# Ripple_PMS.net
KiCad netlist of a schematic drawn in Altium Designer
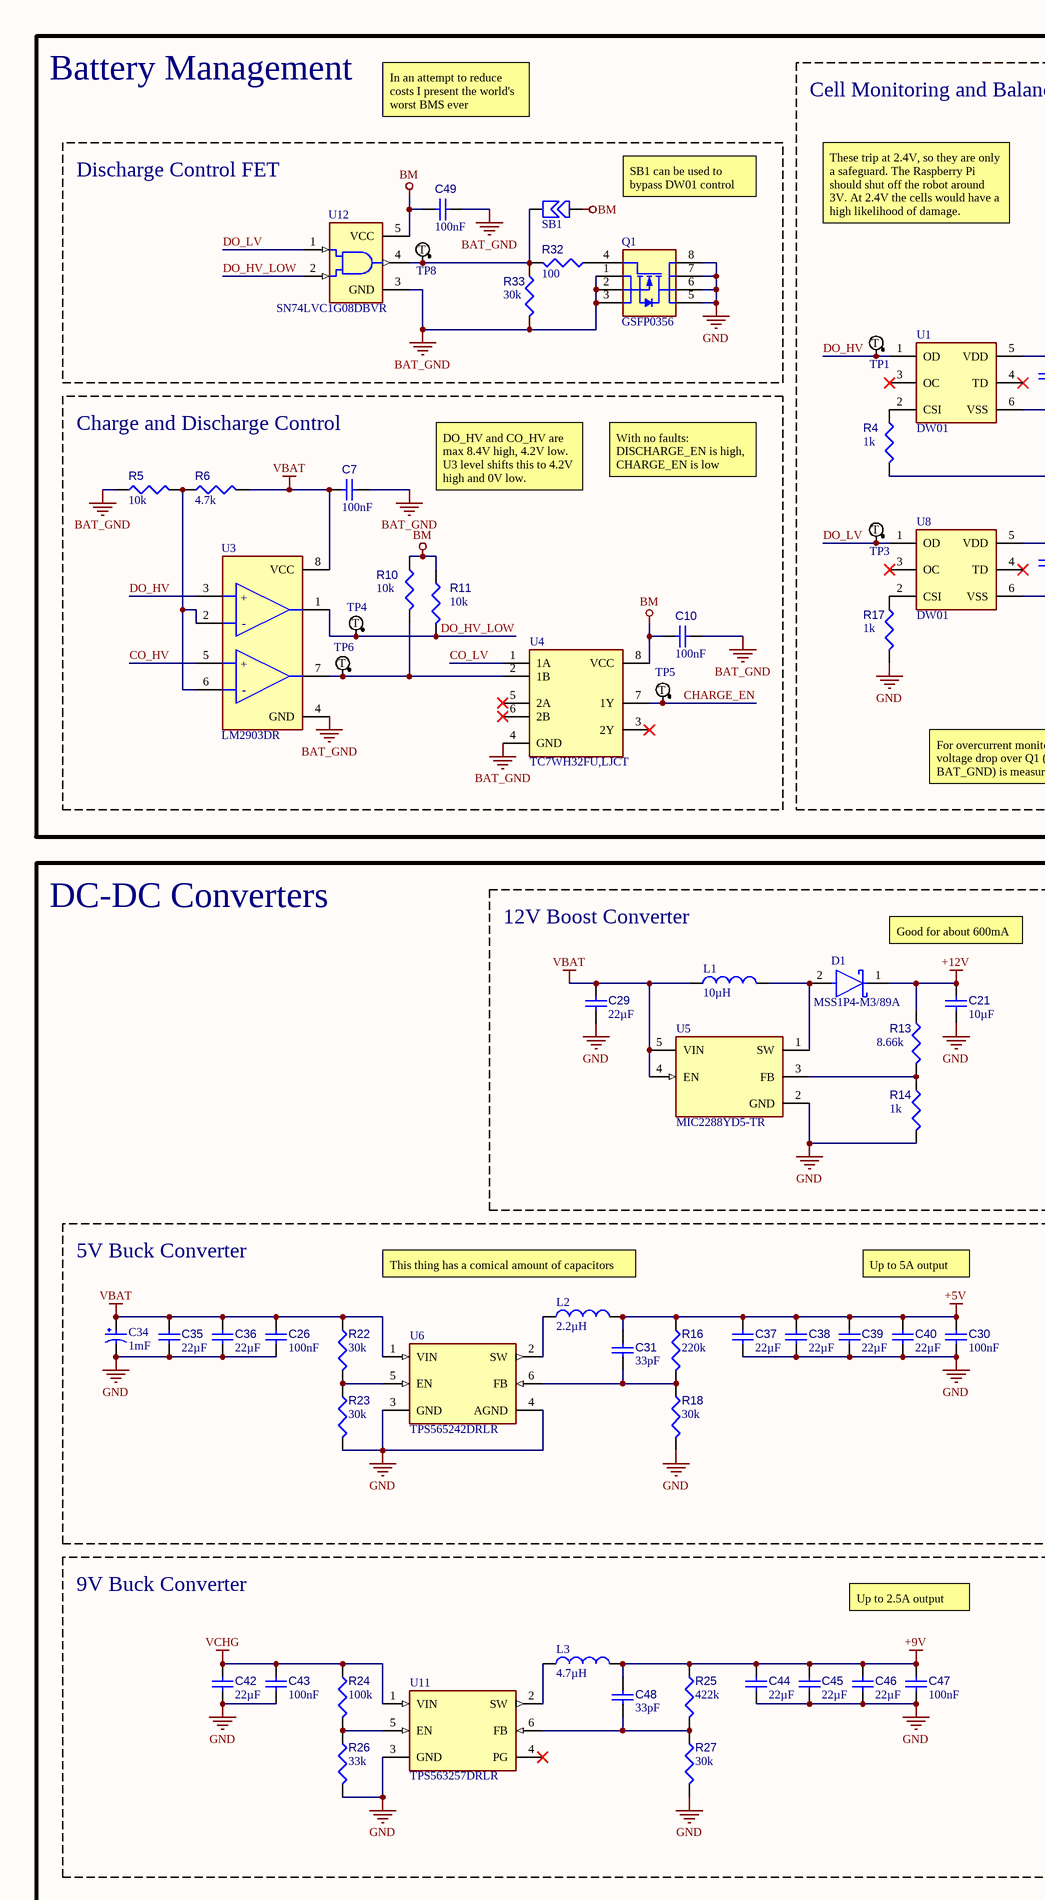
[diagram p0: Ripple_PMS.SchDoc, left]
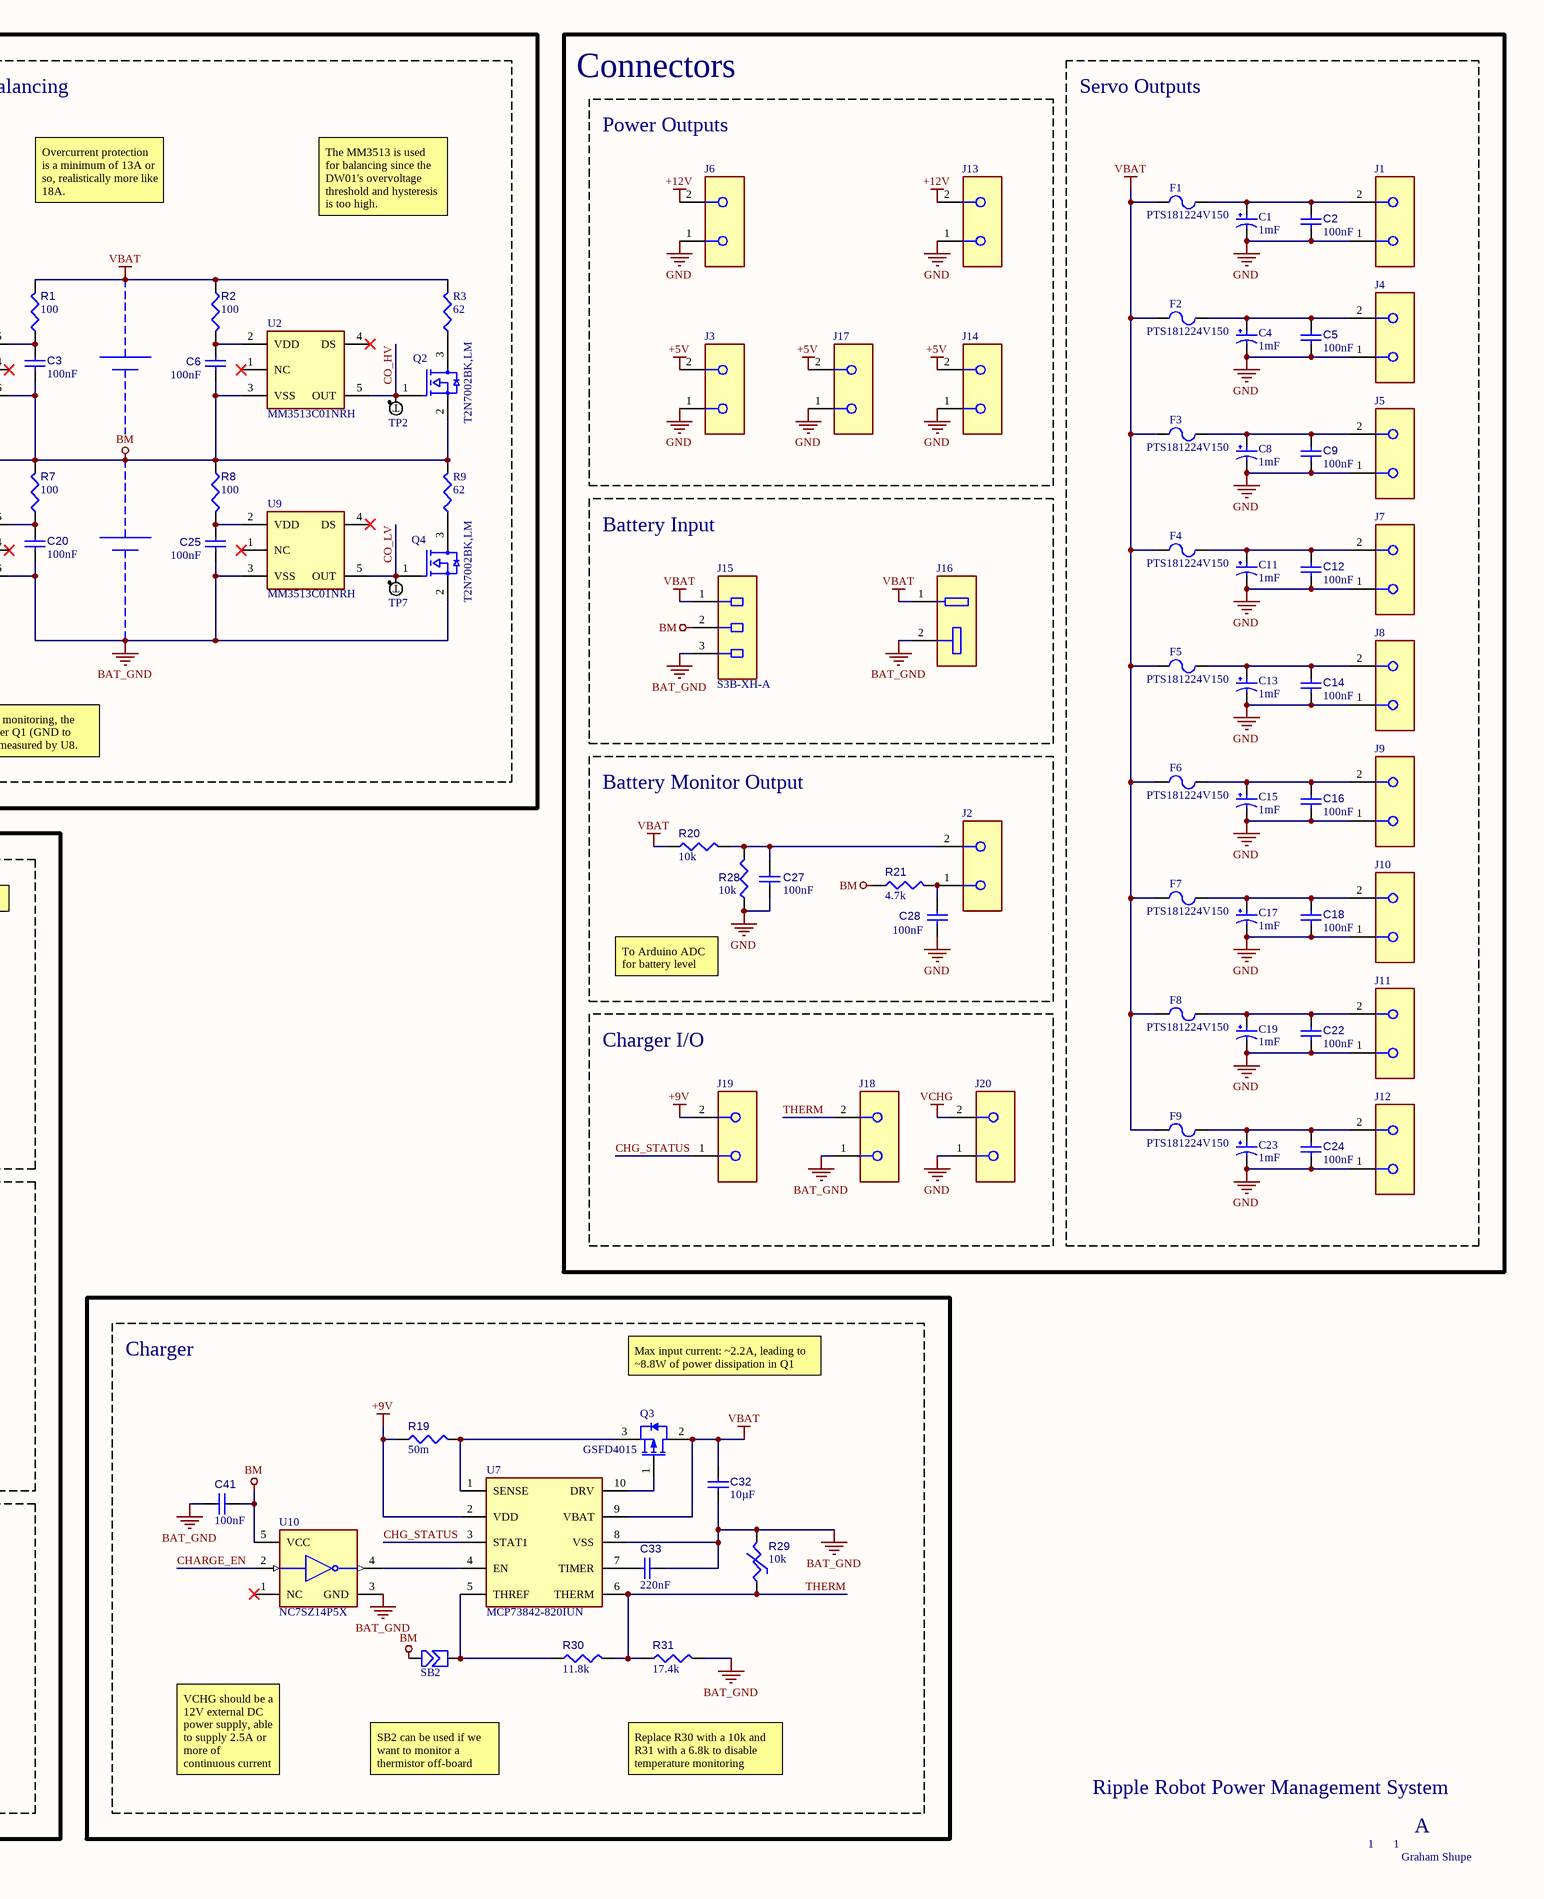
[diagram p1: Ripple_PMS.SchDoc, right]

(export (version "E")
  (design (tool "Eeschema 10.0.6"))
  (components
    (comp (ref "C1")
      (value "1mF")
      (footprint "CAP_YX_10X16_RUB")
      (description "Description")
      (fields
        (field (name "MANUFACTURER_PART_NUMBER") "16ZLH1000MEFC10X16")
        (field (name "COPYRIGHT") "Copyright (C) 2025 Ultra Librarian. All rights reserved.")
      )
      (libsource (lib "Graham Shupe") (part "16ZLH1000MEFC10X16"))
    )
    (comp (ref "C2")
      (value "100nF")
      (footprint "CAPC2013X95X50LL10T25")
      (description "Chip Capacitor, 100 nF, +/- 10%, 50 V, 0805 (2012 Metric)")
      (fields (field (name "TOLERANCE") "10%") (field (name "Comment") "Capacitor 100 nF +/-10% 50 V 0805"))
      (libsource (lib "Graham Shupe") (part "CAP-NP-2"))
    )
    (comp (ref "C3")
      (value "100nF")
      (footprint "CAPC2013X95X50LL10T25")
      (description "Chip Capacitor, 100 nF, +/- 10%, 50 V, 0805 (2012 Metric)")
      (fields (field (name "TOLERANCE") "10%") (field (name "Comment") "Capacitor 100 nF +/-10% 50 V 0805"))
      (libsource (lib "Graham Shupe") (part "CAP-NP-2"))
    )
    (comp (ref "C4")
      (value "1mF")
      (footprint "CAP_YX_10X16_RUB")
      (description "Description")
      (fields
        (field (name "MANUFACTURER_PART_NUMBER") "16ZLH1000MEFC10X16")
        (field (name "COPYRIGHT") "Copyright (C) 2025 Ultra Librarian. All rights reserved.")
      )
      (libsource (lib "Graham Shupe") (part "16ZLH1000MEFC10X16"))
    )
    (comp (ref "C5")
      (value "100nF")
      (footprint "CAPC2013X95X50LL10T25")
      (description "Chip Capacitor, 100 nF, +/- 10%, 50 V, 0805 (2012 Metric)")
      (fields (field (name "TOLERANCE") "10%") (field (name "Comment") "Capacitor 100 nF +/-10% 50 V 0805"))
      (libsource (lib "Graham Shupe") (part "CAP-NP-2"))
    )
    (comp (ref "C6")
      (value "100nF")
      (footprint "CAPC2013X95X50LL10T25")
      (description "Chip Capacitor, 100 nF, +/- 10%, 50 V, 0805 (2012 Metric)")
      (fields (field (name "TOLERANCE") "10%") (field (name "Comment") "Capacitor 100 nF +/-10% 50 V 0805"))
      (libsource (lib "Graham Shupe") (part "CAP-NP-2"))
    )
    (comp (ref "C7")
      (value "100nF")
      (footprint "CAPC2013X95X50LL10T25")
      (description "Chip Capacitor, 100 nF, +/- 10%, 50 V, 0805 (2012 Metric)")
      (fields (field (name "TOLERANCE") "10%") (field (name "Comment") "Capacitor 100 nF +/-10% 50 V 0805"))
      (libsource (lib "Graham Shupe") (part "CAP-NP-2"))
    )
    (comp (ref "C8")
      (value "1mF")
      (footprint "CAP_YX_10X16_RUB")
      (description "Description")
      (fields
        (field (name "MANUFACTURER_PART_NUMBER") "16ZLH1000MEFC10X16")
        (field (name "COPYRIGHT") "Copyright (C) 2025 Ultra Librarian. All rights reserved.")
      )
      (libsource (lib "Graham Shupe") (part "16ZLH1000MEFC10X16"))
    )
    (comp (ref "C9")
      (value "100nF")
      (footprint "CAPC2013X95X50LL10T25")
      (description "Chip Capacitor, 100 nF, +/- 10%, 50 V, 0805 (2012 Metric)")
      (fields (field (name "TOLERANCE") "10%") (field (name "Comment") "Capacitor 100 nF +/-10% 50 V 0805"))
      (libsource (lib "Graham Shupe") (part "CAP-NP-2"))
    )
    (comp (ref "C10")
      (value "100nF")
      (footprint "CAPC2013X95X50LL10T25")
      (description "Chip Capacitor, 100 nF, +/- 10%, 50 V, 0805 (2012 Metric)")
      (fields (field (name "TOLERANCE") "10%") (field (name "Comment") "Capacitor 100 nF +/-10% 50 V 0805"))
      (libsource (lib "Graham Shupe") (part "CAP-NP-2"))
    )
    (comp (ref "C11")
      (value "1mF")
      (footprint "CAP_YX_10X16_RUB")
      (description "Description")
      (fields
        (field (name "MANUFACTURER_PART_NUMBER") "16ZLH1000MEFC10X16")
        (field (name "COPYRIGHT") "Copyright (C) 2025 Ultra Librarian. All rights reserved.")
      )
      (libsource (lib "Graham Shupe") (part "16ZLH1000MEFC10X16"))
    )
    (comp (ref "C12")
      (value "100nF")
      (footprint "CAPC2013X95X50LL10T25")
      (description "Chip Capacitor, 100 nF, +/- 10%, 50 V, 0805 (2012 Metric)")
      (fields (field (name "TOLERANCE") "10%") (field (name "Comment") "Capacitor 100 nF +/-10% 50 V 0805"))
      (libsource (lib "Graham Shupe") (part "CAP-NP-2"))
    )
    (comp (ref "C13")
      (value "1mF")
      (footprint "CAP_YX_10X16_RUB")
      (description "Description")
      (fields
        (field (name "MANUFACTURER_PART_NUMBER") "16ZLH1000MEFC10X16")
        (field (name "COPYRIGHT") "Copyright (C) 2025 Ultra Librarian. All rights reserved.")
      )
      (libsource (lib "Graham Shupe") (part "16ZLH1000MEFC10X16"))
    )
    (comp (ref "C14")
      (value "100nF")
      (footprint "CAPC2013X95X50LL10T25")
      (description "Chip Capacitor, 100 nF, +/- 10%, 50 V, 0805 (2012 Metric)")
      (fields (field (name "TOLERANCE") "10%") (field (name "Comment") "Capacitor 100 nF +/-10% 50 V 0805"))
      (libsource (lib "Graham Shupe") (part "CAP-NP-2"))
    )
    (comp (ref "C15")
      (value "1mF")
      (footprint "CAP_YX_10X16_RUB")
      (description "Description")
      (fields
        (field (name "MANUFACTURER_PART_NUMBER") "16ZLH1000MEFC10X16")
        (field (name "COPYRIGHT") "Copyright (C) 2025 Ultra Librarian. All rights reserved.")
      )
      (libsource (lib "Graham Shupe") (part "16ZLH1000MEFC10X16"))
    )
    (comp (ref "C16")
      (value "100nF")
      (footprint "CAPC2013X95X50LL10T25")
      (description "Chip Capacitor, 100 nF, +/- 10%, 50 V, 0805 (2012 Metric)")
      (fields (field (name "TOLERANCE") "10%") (field (name "Comment") "Capacitor 100 nF +/-10% 50 V 0805"))
      (libsource (lib "Graham Shupe") (part "CAP-NP-2"))
    )
    (comp (ref "C17")
      (value "1mF")
      (footprint "CAP_YX_10X16_RUB")
      (description "Description")
      (fields
        (field (name "MANUFACTURER_PART_NUMBER") "16ZLH1000MEFC10X16")
        (field (name "COPYRIGHT") "Copyright (C) 2025 Ultra Librarian. All rights reserved.")
      )
      (libsource (lib "Graham Shupe") (part "16ZLH1000MEFC10X16"))
    )
    (comp (ref "C18")
      (value "100nF")
      (footprint "CAPC2013X95X50LL10T25")
      (description "Chip Capacitor, 100 nF, +/- 10%, 50 V, 0805 (2012 Metric)")
      (fields (field (name "TOLERANCE") "10%") (field (name "Comment") "Capacitor 100 nF +/-10% 50 V 0805"))
      (libsource (lib "Graham Shupe") (part "CAP-NP-2"))
    )
    (comp (ref "C19")
      (value "1mF")
      (footprint "CAP_YX_10X16_RUB")
      (description "Description")
      (fields
        (field (name "MANUFACTURER_PART_NUMBER") "16ZLH1000MEFC10X16")
        (field (name "COPYRIGHT") "Copyright (C) 2025 Ultra Librarian. All rights reserved.")
      )
      (libsource (lib "Graham Shupe") (part "16ZLH1000MEFC10X16"))
    )
    (comp (ref "C20")
      (value "100nF")
      (footprint "CAPC2013X95X50LL10T25")
      (description "Chip Capacitor, 100 nF, +/- 10%, 50 V, 0805 (2012 Metric)")
      (fields (field (name "TOLERANCE") "10%") (field (name "Comment") "Capacitor 100 nF +/-10% 50 V 0805"))
      (libsource (lib "Graham Shupe") (part "CAP-NP-2"))
    )
    (comp (ref "C21")
      (value "10µF")
      (footprint "CAPC0805(2012)145_L")
      (description "Chip Capacitor, 10µF +/-20%, 25V, 0805, Thickness 1.45 mm")
      (fields (field (name "TOLERANCE") "10%") (field (name "Comment") "Capacitor 10µF +/-20% 25V 0805"))
      (libsource (lib "Graham Shupe") (part "CAP-NP-2"))
    )
    (comp (ref "C22")
      (value "100nF")
      (footprint "CAPC2013X95X50LL10T25")
      (description "Chip Capacitor, 100 nF, +/- 10%, 50 V, 0805 (2012 Metric)")
      (fields (field (name "TOLERANCE") "10%") (field (name "Comment") "Capacitor 100 nF +/-10% 50 V 0805"))
      (libsource (lib "Graham Shupe") (part "CAP-NP-2"))
    )
    (comp (ref "C23")
      (value "1mF")
      (footprint "CAP_YX_10X16_RUB")
      (description "Description")
      (fields
        (field (name "MANUFACTURER_PART_NUMBER") "16ZLH1000MEFC10X16")
        (field (name "COPYRIGHT") "Copyright (C) 2025 Ultra Librarian. All rights reserved.")
      )
      (libsource (lib "Graham Shupe") (part "16ZLH1000MEFC10X16"))
    )
    (comp (ref "C24")
      (value "100nF")
      (footprint "CAPC2013X95X50LL10T25")
      (description "Chip Capacitor, 100 nF, +/- 10%, 50 V, 0805 (2012 Metric)")
      (fields (field (name "TOLERANCE") "10%") (field (name "Comment") "Capacitor 100 nF +/-10% 50 V 0805"))
      (libsource (lib "Graham Shupe") (part "CAP-NP-2"))
    )
    (comp (ref "C25")
      (value "100nF")
      (footprint "CAPC2013X95X50LL10T25")
      (description "Chip Capacitor, 100 nF, +/- 10%, 50 V, 0805 (2012 Metric)")
      (fields (field (name "TOLERANCE") "10%") (field (name "Comment") "Capacitor 100 nF +/-10% 50 V 0805"))
      (libsource (lib "Graham Shupe") (part "CAP-NP-2"))
    )
    (comp (ref "C26")
      (value "100nF")
      (footprint "CAPC2013X95X50LL10T25")
      (description "Chip Capacitor, 100 nF, +/- 10%, 50 V, 0805 (2012 Metric)")
      (fields (field (name "TOLERANCE") "10%") (field (name "Comment") "Capacitor 100 nF +/-10% 50 V 0805"))
      (libsource (lib "Graham Shupe") (part "CAP-NP-2"))
    )
    (comp (ref "C27")
      (value "100nF")
      (footprint "CAPC2013X95X50LL10T25")
      (description "Chip Capacitor, 100 nF, +/- 10%, 50 V, 0805 (2012 Metric)")
      (fields (field (name "TOLERANCE") "10%") (field (name "Comment") "Capacitor 100 nF +/-10% 50 V 0805"))
      (libsource (lib "Graham Shupe") (part "CAP-NP-2"))
    )
    (comp (ref "C28")
      (value "100nF")
      (footprint "CAPC2013X95X50LL10T25")
      (description "Chip Capacitor, 100 nF, +/- 10%, 50 V, 0805 (2012 Metric)")
      (fields (field (name "TOLERANCE") "10%") (field (name "Comment") "Capacitor 100 nF +/-10% 50 V 0805"))
      (libsource (lib "Graham Shupe") (part "CAP-NP-2"))
    )
    (comp (ref "C29")
      (value "22µF")
      (footprint "CAPC0805(2012)145_L")
      (description "Chip Capacitor, 22µF +/-40%, 16V, 0805, Thickness 1.45 mm")
      (fields (field (name "TOLERANCE") "5%") (field (name "Comment") "Capacitor 22µF +/-40% 16V 0805"))
      (libsource (lib "Graham Shupe") (part "CAP-NP-2"))
    )
    (comp (ref "C30")
      (value "100nF")
      (footprint "CAPC2013X95X50LL10T25")
      (description "Chip Capacitor, 100 nF, +/- 10%, 50 V, 0805 (2012 Metric)")
      (fields (field (name "TOLERANCE") "10%") (field (name "Comment") "Capacitor 100 nF +/-10% 50 V 0805"))
      (libsource (lib "Graham Shupe") (part "CAP-NP-2"))
    )
    (comp (ref "C31")
      (value "33pF")
      (footprint "RESC2012X06N")
      (description "0805 33pF")
      (fields (field (name "Comment") "33 pF Capacitor"))
      (libsource (lib "Graham Shupe") (part "CAP-NP-2"))
    )
    (comp (ref "C32")
      (value "10µF")
      (footprint "CAPC0805(2012)145_L")
      (description "Chip Capacitor, 10µF +/-20%, 25V, 0805, Thickness 1.45 mm")
      (fields (field (name "TOLERANCE") "10%") (field (name "Comment") "Capacitor 10µF +/-20% 25V 0805"))
      (libsource (lib "Graham Shupe") (part "CAP-NP-2"))
    )
    (comp (ref "C33")
      (value "220nF")
      (footprint "RESC2012X06N")
      (description "0.22 uF")
      (fields (field (name "Comment") "220 nF Capacitor"))
      (libsource (lib "Graham Shupe") (part "CAP-NP-2"))
    )
    (comp (ref "C34")
      (value "1mF")
      (footprint "CAP_YX_10X16_RUB")
      (description "Description")
      (fields
        (field (name "MANUFACTURER_PART_NUMBER") "16ZLH1000MEFC10X16")
        (field (name "COPYRIGHT") "Copyright (C) 2025 Ultra Librarian. All rights reserved.")
      )
      (libsource (lib "Graham Shupe") (part "16ZLH1000MEFC10X16"))
    )
    (comp (ref "C35")
      (value "22µF")
      (footprint "CAPC0805(2012)145_L")
      (description "Chip Capacitor, 22µF +/-40%, 16V, 0805, Thickness 1.45 mm")
      (fields (field (name "TOLERANCE") "5%") (field (name "Comment") "Capacitor 22µF +/-40% 16V 0805"))
      (libsource (lib "Graham Shupe") (part "CAP-NP-2"))
    )
    (comp (ref "C36")
      (value "22µF")
      (footprint "CAPC0805(2012)145_L")
      (description "Chip Capacitor, 22µF +/-40%, 16V, 0805, Thickness 1.45 mm")
      (fields (field (name "TOLERANCE") "5%") (field (name "Comment") "Capacitor 22µF +/-40% 16V 0805"))
      (libsource (lib "Graham Shupe") (part "CAP-NP-2"))
    )
    (comp (ref "C37")
      (value "22µF")
      (footprint "CAPC0805(2012)145_L")
      (description "Chip Capacitor, 22µF +/-40%, 16V, 0805, Thickness 1.45 mm")
      (fields (field (name "TOLERANCE") "5%") (field (name "Comment") "Capacitor 22µF +/-40% 16V 0805"))
      (libsource (lib "Graham Shupe") (part "CAP-NP-2"))
    )
    (comp (ref "C38")
      (value "22µF")
      (footprint "CAPC0805(2012)145_L")
      (description "Chip Capacitor, 22µF +/-40%, 16V, 0805, Thickness 1.45 mm")
      (fields (field (name "TOLERANCE") "5%") (field (name "Comment") "Capacitor 22µF +/-40% 16V 0805"))
      (libsource (lib "Graham Shupe") (part "CAP-NP-2"))
    )
    (comp (ref "C39")
      (value "22µF")
      (footprint "CAPC0805(2012)145_L")
      (description "Chip Capacitor, 22µF +/-40%, 16V, 0805, Thickness 1.45 mm")
      (fields (field (name "TOLERANCE") "5%") (field (name "Comment") "Capacitor 22µF +/-40% 16V 0805"))
      (libsource (lib "Graham Shupe") (part "CAP-NP-2"))
    )
    (comp (ref "C40")
      (value "22µF")
      (footprint "CAPC0805(2012)145_L")
      (description "Chip Capacitor, 22µF +/-40%, 16V, 0805, Thickness 1.45 mm")
      (fields (field (name "TOLERANCE") "5%") (field (name "Comment") "Capacitor 22µF +/-40% 16V 0805"))
      (libsource (lib "Graham Shupe") (part "CAP-NP-2"))
    )
    (comp (ref "C41")
      (value "100nF")
      (footprint "CAPC2013X95X50LL10T25")
      (description "Chip Capacitor, 100 nF, +/- 10%, 50 V, 0805 (2012 Metric)")
      (fields (field (name "TOLERANCE") "10%") (field (name "Comment") "Capacitor 100 nF +/-10% 50 V 0805"))
      (libsource (lib "Graham Shupe") (part "CAP-NP-2"))
    )
    (comp (ref "C42")
      (value "22µF")
      (footprint "CAPC0805(2012)145_L")
      (description "Chip Capacitor, 22µF +/-40%, 16V, 0805, Thickness 1.45 mm")
      (fields (field (name "TOLERANCE") "5%") (field (name "Comment") "Capacitor 22µF +/-40% 16V 0805"))
      (libsource (lib "Graham Shupe") (part "CAP-NP-2"))
    )
    (comp (ref "C43")
      (value "100nF")
      (footprint "CAPC2013X95X50LL10T25")
      (description "Chip Capacitor, 100 nF, +/- 10%, 50 V, 0805 (2012 Metric)")
      (fields (field (name "TOLERANCE") "10%") (field (name "Comment") "Capacitor 100 nF +/-10% 50 V 0805"))
      (libsource (lib "Graham Shupe") (part "CAP-NP-2"))
    )
    (comp (ref "C44")
      (value "22µF")
      (footprint "CAPC0805(2012)145_L")
      (description "Chip Capacitor, 22µF +/-40%, 16V, 0805, Thickness 1.45 mm")
      (fields (field (name "TOLERANCE") "5%") (field (name "Comment") "Capacitor 22µF +/-40% 16V 0805"))
      (libsource (lib "Graham Shupe") (part "CAP-NP-2"))
    )
    (comp (ref "C45")
      (value "22µF")
      (footprint "CAPC0805(2012)145_L")
      (description "Chip Capacitor, 22µF +/-40%, 16V, 0805, Thickness 1.45 mm")
      (fields (field (name "TOLERANCE") "5%") (field (name "Comment") "Capacitor 22µF +/-40% 16V 0805"))
      (libsource (lib "Graham Shupe") (part "CAP-NP-2"))
    )
    (comp (ref "C46")
      (value "22µF")
      (footprint "CAPC0805(2012)145_L")
      (description "Chip Capacitor, 22µF +/-40%, 16V, 0805, Thickness 1.45 mm")
      (fields (field (name "TOLERANCE") "5%") (field (name "Comment") "Capacitor 22µF +/-40% 16V 0805"))
      (libsource (lib "Graham Shupe") (part "CAP-NP-2"))
    )
    (comp (ref "C47")
      (value "100nF")
      (footprint "CAPC2013X95X50LL10T25")
      (description "Chip Capacitor, 100 nF, +/- 10%, 50 V, 0805 (2012 Metric)")
      (fields (field (name "TOLERANCE") "10%") (field (name "Comment") "Capacitor 100 nF +/-10% 50 V 0805"))
      (libsource (lib "Graham Shupe") (part "CAP-NP-2"))
    )
    (comp (ref "C48")
      (value "33pF")
      (footprint "RESC2012X06N")
      (description "0805 33pF")
      (fields (field (name "Comment") "33 pF Capacitor"))
      (libsource (lib "Graham Shupe") (part "CAP-NP-2"))
    )
    (comp (ref "C49")
      (value "100nF")
      (footprint "CAPC2013X95X50LL10T25")
      (description "Chip Capacitor, 100 nF, +/- 10%, 50 V, 0805 (2012 Metric)")
      (fields (field (name "TOLERANCE") "10%") (field (name "Comment") "Capacitor 100 nF +/-10% 50 V 0805"))
      (libsource (lib "Graham Shupe") (part "CAP-NP-2"))
    )
    (comp (ref "D1")
      (value "MSS1P4-M3/89A")
      (footprint "FP-96591-MFG")
      (description "DIODE SCHOTTKY 40V 1A MICROSMP")
      (fields
        (field (name "OCTOPART") "https://octopart.com/mss1p4-m3%2F89a-vishay-42505723")
        (field (name "MANUFACTURER") "Vishay")
      )
      (libsource (lib "Altium Content Vault") (part "c1678fac7984e62e0809fbf79c06691"))
    )
    (comp (ref "F1")
      (value "PTS181224V150")
      (footprint "FUSE_PTS18126_COB")
      (description "1.5A hold 3A trip")
      (fields
        (field (name "MANUFACTURER_PART_NUMBER") "PTS18126V300")
        (field (name "COPYRIGHT") "Copyright (C) 2025 Ultra Librarian. All rights reserved.")
      )
      (libsource (lib "Graham Shupe") (part "PTS18126V300"))
    )
    (comp (ref "F2")
      (value "PTS181224V150")
      (footprint "FUSE_PTS18126_COB")
      (description "1.5A hold 3A trip")
      (fields
        (field (name "MANUFACTURER_PART_NUMBER") "PTS18126V300")
        (field (name "COPYRIGHT") "Copyright (C) 2025 Ultra Librarian. All rights reserved.")
      )
      (libsource (lib "Graham Shupe") (part "PTS18126V300"))
    )
    (comp (ref "F3")
      (value "PTS181224V150")
      (footprint "FUSE_PTS18126_COB")
      (description "1.5A hold 3A trip")
      (fields
        (field (name "MANUFACTURER_PART_NUMBER") "PTS18126V300")
        (field (name "COPYRIGHT") "Copyright (C) 2025 Ultra Librarian. All rights reserved.")
      )
      (libsource (lib "Graham Shupe") (part "PTS18126V300"))
    )
    (comp (ref "F4")
      (value "PTS181224V150")
      (footprint "FUSE_PTS18126_COB")
      (description "1.5A hold 3A trip")
      (fields
        (field (name "MANUFACTURER_PART_NUMBER") "PTS18126V300")
        (field (name "COPYRIGHT") "Copyright (C) 2025 Ultra Librarian. All rights reserved.")
      )
      (libsource (lib "Graham Shupe") (part "PTS18126V300"))
    )
    (comp (ref "F5")
      (value "PTS181224V150")
      (footprint "FUSE_PTS18126_COB")
      (description "1.5A hold 3A trip")
      (fields
        (field (name "MANUFACTURER_PART_NUMBER") "PTS18126V300")
        (field (name "COPYRIGHT") "Copyright (C) 2025 Ultra Librarian. All rights reserved.")
      )
      (libsource (lib "Graham Shupe") (part "PTS18126V300"))
    )
    (comp (ref "F6")
      (value "PTS181224V150")
      (footprint "FUSE_PTS18126_COB")
      (description "1.5A hold 3A trip")
      (fields
        (field (name "MANUFACTURER_PART_NUMBER") "PTS18126V300")
        (field (name "COPYRIGHT") "Copyright (C) 2025 Ultra Librarian. All rights reserved.")
      )
      (libsource (lib "Graham Shupe") (part "PTS18126V300"))
    )
    (comp (ref "F7")
      (value "PTS181224V150")
      (footprint "FUSE_PTS18126_COB")
      (description "1.5A hold 3A trip")
      (fields
        (field (name "MANUFACTURER_PART_NUMBER") "PTS18126V300")
        (field (name "COPYRIGHT") "Copyright (C) 2025 Ultra Librarian. All rights reserved.")
      )
      (libsource (lib "Graham Shupe") (part "PTS18126V300"))
    )
    (comp (ref "F8")
      (value "PTS181224V150")
      (footprint "FUSE_PTS18126_COB")
      (description "1.5A hold 3A trip")
      (fields
        (field (name "MANUFACTURER_PART_NUMBER") "PTS18126V300")
        (field (name "COPYRIGHT") "Copyright (C) 2025 Ultra Librarian. All rights reserved.")
      )
      (libsource (lib "Graham Shupe") (part "PTS18126V300"))
    )
    (comp (ref "F9")
      (value "PTS181224V150")
      (footprint "FUSE_PTS18126_COB")
      (description "1.5A hold 3A trip")
      (fields
        (field (name "MANUFACTURER_PART_NUMBER") "PTS18126V300")
        (field (name "COPYRIGHT") "Copyright (C) 2025 Ultra Librarian. All rights reserved.")
      )
      (libsource (lib "Graham Shupe") (part "PTS18126V300"))
    )
    (comp (ref "J1")
      (value "ServoBreakout2Pin")
      (footprint "New footprint 1")
      (description "for ripple bot")
      (libsource (lib "Graham Shupe") (part "New symbol 1"))
    )
    (comp (ref "J2")
      (value "ServoBreakout2Pin")
      (footprint "New footprint 1")
      (description "for ripple bot")
      (libsource (lib "Graham Shupe") (part "New symbol 1"))
    )
    (comp (ref "J3")
      (value "ServoBreakout2Pin")
      (footprint "New footprint 1")
      (description "for ripple bot")
      (libsource (lib "Graham Shupe") (part "New symbol 1"))
    )
    (comp (ref "J4")
      (value "ServoBreakout2Pin")
      (footprint "New footprint 1")
      (description "for ripple bot")
      (libsource (lib "Graham Shupe") (part "New symbol 1"))
    )
    (comp (ref "J5")
      (value "ServoBreakout2Pin")
      (footprint "New footprint 1")
      (description "for ripple bot")
      (libsource (lib "Graham Shupe") (part "New symbol 1"))
    )
    (comp (ref "J6")
      (value "ServoBreakout2Pin")
      (footprint "New footprint 1")
      (description "for ripple bot")
      (libsource (lib "Graham Shupe") (part "New symbol 1"))
    )
    (comp (ref "J7")
      (value "ServoBreakout2Pin")
      (footprint "New footprint 1")
      (description "for ripple bot")
      (libsource (lib "Graham Shupe") (part "New symbol 1"))
    )
    (comp (ref "J8")
      (value "ServoBreakout2Pin")
      (footprint "New footprint 1")
      (description "for ripple bot")
      (libsource (lib "Graham Shupe") (part "New symbol 1"))
    )
    (comp (ref "J9")
      (value "ServoBreakout2Pin")
      (footprint "New footprint 1")
      (description "for ripple bot")
      (libsource (lib "Graham Shupe") (part "New symbol 1"))
    )
    (comp (ref "J10")
      (value "ServoBreakout2Pin")
      (footprint "New footprint 1")
      (description "for ripple bot")
      (libsource (lib "Graham Shupe") (part "New symbol 1"))
    )
    (comp (ref "J11")
      (value "ServoBreakout2Pin")
      (footprint "New footprint 1")
      (description "for ripple bot")
      (libsource (lib "Graham Shupe") (part "New symbol 1"))
    )
    (comp (ref "J12")
      (value "ServoBreakout2Pin")
      (footprint "New footprint 1")
      (description "for ripple bot")
      (libsource (lib "Graham Shupe") (part "New symbol 1"))
    )
    (comp (ref "J13")
      (value "ServoBreakout2Pin")
      (footprint "New footprint 1")
      (description "for ripple bot")
      (libsource (lib "Graham Shupe") (part "New symbol 1"))
    )
    (comp (ref "J14")
      (value "ServoBreakout2Pin")
      (footprint "New footprint 1")
      (description "for ripple bot")
      (libsource (lib "Graham Shupe") (part "New symbol 1"))
    )
    (comp (ref "J15")
      (value "S3B-XH-A")
      (footprint "FP-S3B-XH-A-1_LF_SN-MFG")
      (description "Header for PCB; pitch 2.50mm; 3-contacts; THT; male; side entry; 250V/3A")
      (libsource (lib "Graham Shupe") (part "0d3f023dd272f625e17a2be33dea85f"))
    )
    (comp (ref "J16")
      (value "Deans Connector")
      (footprint "Deans Connector-Footprint-1")
      (description "T Plug battery connector through-hole")
      (libsource (lib "Graham Shupe") (part "Deans Connector-Symbol-1"))
    )
    (comp (ref "J17")
      (value "ServoBreakout2Pin")
      (footprint "New footprint 1")
      (description "for ripple bot")
      (libsource (lib "Graham Shupe") (part "New symbol 1"))
    )
    (comp (ref "J18")
      (value "ServoBreakout2Pin")
      (footprint "New footprint 1")
      (description "for ripple bot")
      (libsource (lib "Graham Shupe") (part "New symbol 1"))
    )
    (comp (ref "J19")
      (value "ServoBreakout2Pin")
      (footprint "New footprint 1")
      (description "for ripple bot")
      (libsource (lib "Graham Shupe") (part "New symbol 1"))
    )
    (comp (ref "J20")
      (value "ServoBreakout2Pin")
      (footprint "New footprint 1")
      (description "for ripple bot")
      (libsource (lib "Graham Shupe") (part "New symbol 1"))
    )
    (comp (ref "L1")
      (value "10µH")
      (footprint "BOUR-CM322522_V")
      (description "Chip Inductor, 10 uH, +/- 20%, -40 to 125 degC, 1210 (3225 Metric), RoHS, Tape and Reel")
      (fields (field (name "MANUFACTURER") "Bourns") (field (name "Comment") "CBC3225T100MR"))
      (libsource (lib "Graham Shupe") (part "Copy of BOUR-IND-2A"))
    )
    (comp (ref "L2")
      (value "2.2µH")
      (footprint "IND_SDES064T_CYN")
      (description "No Description Available")
      (fields
        (field (name "MANUFACTURER_PART_NUMBER") "SDES064T-2R2MS")
        (field (name "COPYRIGHT") "Copyright (C) 2026 Ultra Librarian. All rights reserved.")
      )
      (libsource (lib "Graham Shupe") (part "SDES064T-2R2MS"))
    )
    (comp (ref "L3")
      (value "4.7µH")
      (footprint "IND_VLS6045EX-4R7M_TDK")
      (description "4.7uH inductor")
      (fields
        (field (name "MANUFACTURER_PART_NUMBER") "VLS6045EX-4R7M")
        (field (name "COPYRIGHT") "Copyright (C) 2025 Ultra Librarian. All rights reserved.")
      )
      (libsource (lib "Graham Shupe") (part "VLS6045EX-4R7M"))
    )
    (comp (ref "Q1")
      (value "GSFP0356")
      (footprint "PPAK5X6-8L_GAS")
      (description "55A N-ch MOSFET, 47W PD@Tc=25")
      (fields
        (field (name "MANUFACTURER_PART_NUMBER") "GSFP1080")
        (field (name "COPYRIGHT") "Copyright (C) 2025 Ultra Librarian. All rights reserved.")
      )
      (libsource (lib "Graham Shupe") (part "GSFP1080"))
    )
    (comp (ref "Q2")
      (value "T2N7002BK,LM")
      (footprint "SOT23_TOS")
      (description "N-ch MOSFET, 60 V, 0.4 A, SOT-23(SOT23)")
      (fields (field (name "COPYRIGHT") "Copyright (C) 2026 Ultra Librarian. All rights reserved."))
      (libsource (lib "Graham Shupe") (part "T2N7002BK,LM"))
    )
    (comp (ref "Q3")
      (value "GSFD4015")
      (footprint "PMOSGDS_TO-252_DPAK_GAS")
      (description "40A P-channel MOSFET, 80W PD@Tc25")
      (fields
        (field (name "MANUFACTURER_PART_NUMBER") "GSFD6959")
        (field (name "COPYRIGHT") "Copyright (C) 2025 Ultra Librarian. All rights reserved.")
      )
      (libsource (lib "Graham Shupe") (part "GSFD6959"))
    )
    (comp (ref "Q4")
      (value "T2N7002BK,LM")
      (footprint "SOT23_TOS")
      (description "N-ch MOSFET, 60 V, 0.4 A, SOT-23(SOT23)")
      (fields (field (name "COPYRIGHT") "Copyright (C) 2026 Ultra Librarian. All rights reserved."))
      (libsource (lib "Graham Shupe") (part "T2N7002BK,LM"))
    )
    (comp (ref "R1")
      (value "100")
      (footprint "RESC2012X06N")
      (description "0805")
      (fields (field (name "Comment") "100R resistor"))
      (libsource (lib "Graham Shupe") (part "RES-2"))
    )
    (comp (ref "R2")
      (value "100")
      (footprint "RESC2012X06N")
      (description "0805")
      (fields (field (name "Comment") "100R resistor"))
      (libsource (lib "Graham Shupe") (part "RES-2"))
    )
    (comp (ref "R3")
      (value "62")
      (footprint "RES_R1632_ROM")
      (description "1.5 W")
      (fields
        (field (name "POWER") "1.5W")
        (field (name "MANUFACTURER_PART_NUMBER") "LTR18EZPJ620")
        (field (name "COPYRIGHT") "Copyright (C) 2026 Ultra Librarian. All rights reserved.")
      )
      (libsource (lib "Graham Shupe") (part "LTR18EZPJ620"))
    )
    (comp (ref "R4")
      (value "1k")
      (footprint "RESC0805(2012)_L")
      (description "Chip Resistor, 1 kOhms, +/-5%, 125 mW, -55 to 155 degC, 0805")
      (fields (field (name "TOLERANCE") "5%") (field (name "POWER") "125mW"))
      (libsource (lib "Graham Shupe") (part "RES-2"))
    )
    (comp (ref "R5")
      (value "10k")
      (footprint "RESC2013X50X35ML15T15")
      (description "Chip Resistor, 10 KOhm, +/- 1%, 125 mW, -55 to 155 degC, 0805 (2012 Metric)")
      (fields (field (name "TOLERANCE") "1%") (field (name "POWER") "125mW"))
      (libsource (lib "Graham Shupe") (part "RES-2"))
    )
    (comp (ref "R6")
      (value "4.7k")
      (footprint "RESC2013X70X40ML20T20")
      (description "Chip Resistor, 4.7 KOhm, +/- 1%, 0.125 W, -55 to 155 degC, 0805 (2012 Metric)")
      (fields (field (name "POWER") "125mW") (field (name "TOLERANCE") "1%"))
      (libsource (lib "Graham Shupe") (part "RES-2"))
    )
    (comp (ref "R7")
      (value "100")
      (footprint "RESC2012X06N")
      (description "0805")
      (fields (field (name "Comment") "100R resistor"))
      (libsource (lib "Graham Shupe") (part "RES-2"))
    )
    (comp (ref "R8")
      (value "100")
      (footprint "RESC2012X06N")
      (description "0805")
      (fields (field (name "Comment") "100R resistor"))
      (libsource (lib "Graham Shupe") (part "RES-2"))
    )
    (comp (ref "R9")
      (value "62")
      (footprint "RES_R1632_ROM")
      (description "1.5 W")
      (fields
        (field (name "POWER") "1.5W")
        (field (name "MANUFACTURER_PART_NUMBER") "LTR18EZPJ620")
        (field (name "COPYRIGHT") "Copyright (C) 2026 Ultra Librarian. All rights reserved.")
      )
      (libsource (lib "Graham Shupe") (part "LTR18EZPJ620"))
    )
    (comp (ref "R10")
      (value "10k")
      (footprint "RESC2013X50X35ML15T15")
      (description "Chip Resistor, 10 KOhm, +/- 1%, 125 mW, -55 to 155 degC, 0805 (2012 Metric)")
      (fields (field (name "TOLERANCE") "1%") (field (name "POWER") "125mW"))
      (libsource (lib "Graham Shupe") (part "RES-2"))
    )
    (comp (ref "R11")
      (value "10k")
      (footprint "RESC2013X50X35ML15T15")
      (description "Chip Resistor, 10 KOhm, +/- 1%, 125 mW, -55 to 155 degC, 0805 (2012 Metric)")
      (fields (field (name "TOLERANCE") "1%") (field (name "POWER") "125mW"))
      (libsource (lib "Graham Shupe") (part "RES-2"))
    )
    (comp (ref "R13")
      (value "8.66k")
      (footprint "RESC2012X06N")
      (description "0805")
      (fields (field (name "Comment") "8.66 kOhm Resistor"))
      (libsource (lib "Graham Shupe") (part "RES-2"))
    )
    (comp (ref "R14")
      (value "1k")
      (footprint "RESC0805(2012)_L")
      (description "Chip Resistor, 1 kOhms, +/-5%, 125 mW, -55 to 155 degC, 0805")
      (fields (field (name "TOLERANCE") "5%") (field (name "POWER") "125mW"))
      (libsource (lib "Graham Shupe") (part "RES-2"))
    )
    (comp (ref "R16")
      (value "220k")
      (footprint "RESC2012X06N")
      (description "0805")
      (fields (field (name "Comment") "220k Resistor"))
      (libsource (lib "Graham Shupe") (part "RES-2"))
    )
    (comp (ref "R17")
      (value "1k")
      (footprint "RESC0805(2012)_L")
      (description "Chip Resistor, 1 kOhms, +/-5%, 125 mW, -55 to 155 degC, 0805")
      (fields (field (name "TOLERANCE") "5%") (field (name "POWER") "125mW"))
      (libsource (lib "Graham Shupe") (part "RES-2"))
    )
    (comp (ref "R18")
      (value "30k")
      (footprint "RESC2012X06N")
      (description "0805")
      (fields (field (name "Comment") "30k Resistor"))
      (libsource (lib "Graham Shupe") (part "RES-2"))
    )
    (comp (ref "R19")
      (value "50m")
      (footprint "RESC2014X06N")
      (description "3/4W 0.05R")
      (fields (field (name "POWER") "750mW") (field (name "Comment") "50 mOhm Sense Resistor"))
      (libsource (lib "Graham Shupe") (part "RES-2"))
    )
    (comp (ref "R20")
      (value "10k")
      (footprint "RESC2013X50X35ML15T15")
      (description "Chip Resistor, 10 KOhm, +/- 1%, 125 mW, -55 to 155 degC, 0805 (2012 Metric)")
      (fields (field (name "TOLERANCE") "1%") (field (name "POWER") "125mW"))
      (libsource (lib "Graham Shupe") (part "RES-2"))
    )
    (comp (ref "R21")
      (value "4.7k")
      (footprint "RESC2013X70X40ML20T20")
      (description "Chip Resistor, 4.7 KOhm, +/- 1%, 0.125 W, -55 to 155 degC, 0805 (2012 Metric)")
      (fields (field (name "POWER") "125mW") (field (name "TOLERANCE") "1%"))
      (libsource (lib "Graham Shupe") (part "RES-2"))
    )
    (comp (ref "R22")
      (value "30k")
      (footprint "RESC2012X06N")
      (description "0805")
      (fields (field (name "Comment") "30k Resistor"))
      (libsource (lib "Graham Shupe") (part "RES-2"))
    )
    (comp (ref "R23")
      (value "30k")
      (footprint "RESC2012X06N")
      (description "0805")
      (fields (field (name "Comment") "30k Resistor"))
      (libsource (lib "Graham Shupe") (part "RES-2"))
    )
    (comp (ref "R24")
      (value "100k")
      (footprint "RESC2013X70X40ML20T20")
      (description "Chip Resistor, 100 KOhm, +/- 1%, 0.125 W, -55 to 155 degC, 0805 (2012 Metric)")
      (fields (field (name "POWER") "125mW") (field (name "TOLERANCE") "1%"))
      (libsource (lib "Graham Shupe") (part "RES-2"))
    )
    (comp (ref "R25")
      (value "422k")
      (footprint "RESC2012X06N")
      (description "0805")
      (fields (field (name "Comment") "422k Resistor"))
      (libsource (lib "Graham Shupe") (part "RES-2"))
    )
    (comp (ref "R26")
      (value "33k")
      (footprint "RESC2012X06N")
      (description "0805")
      (fields (field (name "POWER") "125mW") (field (name "Comment") "33k ohm Resistor"))
      (libsource (lib "Graham Shupe") (part "RES-2"))
    )
    (comp (ref "R27")
      (value "30k")
      (footprint "RESC2012X06N")
      (description "0805")
      (fields (field (name "Comment") "30k Resistor"))
      (libsource (lib "Graham Shupe") (part "RES-2"))
    )
    (comp (ref "R28")
      (value "10k")
      (footprint "RESC2013X50X35ML15T15")
      (description "Chip Resistor, 10 KOhm, +/- 1%, 125 mW, -55 to 155 degC, 0805 (2012 Metric)")
      (fields (field (name "TOLERANCE") "1%") (field (name "POWER") "125mW"))
      (libsource (lib "Graham Shupe") (part "RES-2"))
    )
    (comp (ref "R29")
      (value "10k")
      (footprint "RESC1608X06N")
      (description "0603 10k@25C thermistor")
      (fields (field (name "Comment") "NTC Thermistor 10k"))
      (libsource (lib "Graham Shupe") (part "Copy of RES-2"))
    )
    (comp (ref "R30")
      (value "11.8k")
      (footprint "RESC2012X06N")
      (description "0805")
      (fields (field (name "Comment") "11.8k Resistor"))
      (libsource (lib "Graham Shupe") (part "RES-2"))
    )
    (comp (ref "R31")
      (value "17.4k")
      (footprint "RESC2012X06N")
      (description "0805")
      (fields (field (name "Comment") "17.4k Resistor"))
      (libsource (lib "Graham Shupe") (part "RES-2"))
    )
    (comp (ref "R32")
      (value "100")
      (footprint "RESC2012X06N")
      (description "0805")
      (fields (field (name "Comment") "100R resistor"))
      (libsource (lib "Graham Shupe") (part "RES-2"))
    )
    (comp (ref "R33")
      (value "30k")
      (footprint "RESC2012X06N")
      (description "0805")
      (fields (field (name "Comment") "30k Resistor"))
      (libsource (lib "Graham Shupe") (part "RES-2"))
    )
    (comp (ref "SB1")
      (value "Solder Jumper NO")
      (footprint "RESC1608X06N")
      (description "Normally Open")
      (libsource (lib "Graham Shupe") (part "Solder Jumper NO-Symbol-1"))
    )
    (comp (ref "SB2")
      (value "Solder Jumper NO")
      (footprint "RESC1608X06N")
      (description "Normally Open")
      (libsource (lib "Graham Shupe") (part "Solder Jumper NO-Symbol-1"))
    )
    (comp (ref "TP1")
      (value "Round Pad Testpoint")
      (footprint "Round Pad Testpoint-Footprint-1")
      (description "2mm pad with no through hole")
      (libsource (lib "Graham Shupe") (part "Round Pad Testpoint-Symbol-1"))
    )
    (comp (ref "TP2")
      (value "Round Pad Testpoint")
      (footprint "Round Pad Testpoint-Footprint-1")
      (description "2mm pad with no through hole")
      (libsource (lib "Graham Shupe") (part "Round Pad Testpoint-Symbol-1"))
    )
    (comp (ref "TP3")
      (value "Round Pad Testpoint")
      (footprint "Round Pad Testpoint-Footprint-1")
      (description "2mm pad with no through hole")
      (libsource (lib "Graham Shupe") (part "Round Pad Testpoint-Symbol-1"))
    )
    (comp (ref "TP4")
      (value "Round Pad Testpoint")
      (footprint "Round Pad Testpoint-Footprint-1")
      (description "2mm pad with no through hole")
      (libsource (lib "Graham Shupe") (part "Round Pad Testpoint-Symbol-1"))
    )
    (comp (ref "TP5")
      (value "Round Pad Testpoint")
      (footprint "Round Pad Testpoint-Footprint-1")
      (description "2mm pad with no through hole")
      (libsource (lib "Graham Shupe") (part "Round Pad Testpoint-Symbol-1"))
    )
    (comp (ref "TP6")
      (value "Round Pad Testpoint")
      (footprint "Round Pad Testpoint-Footprint-1")
      (description "2mm pad with no through hole")
      (libsource (lib "Graham Shupe") (part "Round Pad Testpoint-Symbol-1"))
    )
    (comp (ref "TP7")
      (value "Round Pad Testpoint")
      (footprint "Round Pad Testpoint-Footprint-1")
      (description "2mm pad with no through hole")
      (libsource (lib "Graham Shupe") (part "Round Pad Testpoint-Symbol-1"))
    )
    (comp (ref "TP8")
      (value "Round Pad Testpoint")
      (footprint "Round Pad Testpoint-Footprint-1")
      (description "2mm pad with no through hole")
      (libsource (lib "Graham Shupe") (part "Round Pad Testpoint-Symbol-1"))
    )
    (comp (ref "U1")
      (value "DW01")
      (footprint "SOT95P280X130-6N")
      (description "Battery protection IC, 4.25V overvoltage, 2.4V undervoltage")
      (libsource (lib "") (part "New symbol 1_1"))
    )
    (comp (ref "U2")
      (value "MM3513C01NRH")
      (footprint "SOT95P280X130-5N")
      (description "Cell overvoltage monitor, 4.2V trip")
      (libsource (lib "Graham Shupe") (part "MM3513C01NRH-Symbol-1"))
    )
    (comp (ref "U3")
      (value "LM2903DR")
      (footprint "FP-D0008A-IPC_B")
      (description "IC COMPARATOR 2 DIFF 8SOIC \"Comparator General Purpose Open-Collector, Rail-to-Rail 8-SOIC\"")
      (libsource (lib "Graham Shupe") (part "LM2903DR-Symbol-1"))
    )
    (comp (ref "U4")
      (value "TC7WH32FU,LJCT")
      (footprint "SM8_TOS")
      (description "2-CH OR Gate")
      (fields
        (field (name "MANUFACTURER_PART_NUMBER") "TC7WH32FU,LJ(CT")
        (field (name "COPYRIGHT") "Copyright (C) 2025 Ultra Librarian. All rights reserved.")
      )
      (libsource (lib "Graham Shupe") (part "TC7WH32FU,LJCT"))
    )
    (comp (ref "U5")
      (value "MIC2288YD5-TR")
      (footprint "FP-TSOT-5LD-PL-1-IPC_B")
      (description "DC-DC Switching Regulator, Boost, 2.5V to 10V in, 3.6V to 34V out, 1A out, SOT-23-5")
      (libsource (lib "Graham Shupe") (part "8b40e419ffb951c8150a61de73387bc"))
    )
    (comp (ref "U6")
      (value "TPS565242DRLR")
      (footprint "SOT6_DRL_TEX")
      (fields (field (name "COPYRIGHT") "Copyright (C) 2026 Ultra Librarian. All rights reserved."))
      (libsource (lib "Graham Shupe") (part "TPS565242DRLR"))
    )
    (comp (ref "U7")
      (value "MCP73842-820IUN")
      (footprint "MSOP10_MC_MCH")
      (description "8.2V 2 cell battery charger")
      (fields
        (field (name "MANUFACTURER_PART_NUMBER") "MCP73842-820I/UN")
        (field (name "COPYRIGHT") "Copyright (C) 2025 Ultra Librarian. All rights reserved.")
      )
      (libsource (lib "Graham Shupe") (part "MCP73842-820IUN"))
    )
    (comp (ref "U8")
      (value "DW01")
      (footprint "SOT95P280X130-6N")
      (description "Battery protection IC, 4.25V overvoltage, 2.4V undervoltage")
      (libsource (lib "") (part "New symbol 1_1"))
    )
    (comp (ref "U9")
      (value "MM3513C01NRH")
      (footprint "SOT95P280X130-5N")
      (description "Cell overvoltage monitor, 4.2V trip")
      (libsource (lib "Graham Shupe") (part "MM3513C01NRH-Symbol-1"))
    )
    (comp (ref "U10")
      (value "NC7SZ14P5X")
      (footprint "FP-419AC-01-IPC_C")
      (description "IC INVERTER SCHMITT 1CH SC70-5")
      (fields
        (field (name "MANUFACTURER") "ON Semiconductor")
        (field (name "OCTOPART") "https://octopart.com/nc7sz14p5x-on+semiconductor-84330759")
      )
      (libsource (lib "Altium Content Vault") (part "51b7ecfa9d3d36e34a3de78e4e842ae"))
    )
    (comp (ref "U11")
      (value "TPS563257DRLR")
      (footprint "SOT6_DRL_TEX")
      (fields (field (name "COPYRIGHT") "Copyright (C) 2026 Ultra Librarian. All rights reserved."))
      (libsource (lib "Graham Shupe") (part "TPS563257DRLR"))
    )
    (comp (ref "U12")
      (value "SN74LVC1G08DBVR")
      (footprint "DBV0005A_L")
      (description "AND Gate, LVC/LCX/Z Series, 1-Func, 2-Input, CMOS, PDSO5")
      (libsource (lib "Graham Shupe") (part "TI-SN74XXX1X08-5"))
    )
  )
  (nets
    (net (code "1") (name "+5V") (class "Default")
      (node (ref "C30") (pin "1") (pinfunction "1_1") (pintype "passive"))
      (node (ref "C31") (pin "1") (pinfunction "1_1") (pintype "passive"))
      (node (ref "C37") (pin "1") (pinfunction "1_1") (pintype "passive"))
      (node (ref "C38") (pin "1") (pinfunction "1_1") (pintype "passive"))
      (node (ref "C39") (pin "1") (pinfunction "1_1") (pintype "passive"))
      (node (ref "C40") (pin "1") (pinfunction "1_1") (pintype "passive"))
      (node (ref "J14") (pin "2") (pinfunction "2_2") (pintype "passive"))
      (node (ref "J17") (pin "2") (pinfunction "2_2") (pintype "passive"))
      (node (ref "J3") (pin "2") (pinfunction "2_2") (pintype "passive"))
      (node (ref "L2") (pin "2") (pinfunction "2_2") (pintype "passive"))
      (node (ref "R16") (pin "1") (pinfunction "1_1") (pintype "passive"))
    )
    (net (code "2") (name "+9V") (class "Default")
      (node (ref "C44") (pin "1") (pinfunction "1_1") (pintype "passive"))
      (node (ref "C45") (pin "1") (pinfunction "1_1") (pintype "passive"))
      (node (ref "C46") (pin "1") (pinfunction "1_1") (pintype "passive"))
      (node (ref "C47") (pin "1") (pinfunction "1_1") (pintype "passive"))
      (node (ref "C48") (pin "1") (pinfunction "1_1") (pintype "passive"))
      (node (ref "J19") (pin "2") (pinfunction "2_2") (pintype "passive"))
      (node (ref "L3") (pin "1") (pinfunction "1_1") (pintype "passive"))
      (node (ref "R19") (pin "1") (pinfunction "1_1") (pintype "passive"))
      (node (ref "R25") (pin "1") (pinfunction "1_1") (pintype "passive"))
      (node (ref "U7") (pin "2") (pinfunction "VDD_2") (pintype "passive"))
    )
    (net (code "3") (name "+12V") (class "Default")
      (node (ref "C21") (pin "1") (pinfunction "1_1") (pintype "passive"))
      (node (ref "D1") (pin "1") (pinfunction "C_1") (pintype "passive"))
      (node (ref "J13") (pin "2") (pinfunction "2_2") (pintype "passive"))
      (node (ref "J6") (pin "2") (pinfunction "2_2") (pintype "passive"))
      (node (ref "R13") (pin "1") (pinfunction "1_1") (pintype "passive"))
    )
    (net (code "4") (name "/CHARGE_EN") (class "Default")
      (node (ref "TP5") (pin "1") (pinfunction "1_1") (pintype "passive"))
      (node (ref "U10") (pin "2") (pinfunction "A_2") (pintype "input"))
      (node (ref "U4") (pin "7") (pinfunction "1Y_7") (pintype "passive"))
    )
    (net (code "5") (name "/CHG_STATUS") (class "Default")
      (node (ref "J19") (pin "1") (pinfunction "1_1") (pintype "passive"))
      (node (ref "U7") (pin "3") (pinfunction "STAT1_3") (pintype "passive"))
    )
    (net (code "6") (name "/CO_HV") (class "Default")
      (node (ref "Q2") (pin "1") (pinfunction "G_1") (pintype "passive"))
      (node (ref "TP2") (pin "1") (pinfunction "1_1") (pintype "passive"))
      (node (ref "U2") (pin "5") (pinfunction "OUT_5") (pintype "passive"))
      (node (ref "U3") (pin "5") (pinfunction "5_5") (pintype "passive"))
    )
    (net (code "7") (name "/CO_LV") (class "Default")
      (node (ref "Q4") (pin "1") (pinfunction "G_1") (pintype "passive"))
      (node (ref "TP7") (pin "1") (pinfunction "1_1") (pintype "passive"))
      (node (ref "U4") (pin "1") (pinfunction "1A_1") (pintype "passive"))
      (node (ref "U9") (pin "5") (pinfunction "OUT_5") (pintype "passive"))
    )
    (net (code "8") (name "/DO_HV") (class "Default")
      (node (ref "TP1") (pin "1") (pinfunction "1_1") (pintype "passive"))
      (node (ref "U1") (pin "1") (pinfunction "OD_1") (pintype "passive"))
      (node (ref "U3") (pin "3") (pinfunction "3_3") (pintype "passive"))
    )
    (net (code "9") (name "/DO_HV_LOW") (class "Default")
      (node (ref "R11") (pin "2") (pinfunction "2_2") (pintype "passive"))
      (node (ref "TP4") (pin "1") (pinfunction "1_1") (pintype "passive"))
      (node (ref "U12") (pin "2") (pinfunction "B_2") (pintype "input"))
      (node (ref "U3") (pin "1") (pinfunction "1_1") (pintype "passive"))
    )
    (net (code "10") (name "/DO_LV") (class "Default")
      (node (ref "TP3") (pin "1") (pinfunction "1_1") (pintype "passive"))
      (node (ref "U12") (pin "1") (pinfunction "A_1") (pintype "input"))
      (node (ref "U8") (pin "1") (pinfunction "OD_1") (pintype "passive"))
    )
    (net (code "11") (name "/THERM") (class "Default")
      (node (ref "J18") (pin "2") (pinfunction "2_2") (pintype "passive"))
      (node (ref "R29") (pin "1") (pinfunction "1_1") (pintype "passive"))
      (node (ref "R30") (pin "2") (pinfunction "2_2") (pintype "passive"))
      (node (ref "R31") (pin "1") (pinfunction "1_1") (pintype "passive"))
      (node (ref "U7") (pin "6") (pinfunction "THERM_6") (pintype "passive"))
    )
    (net (code "12") (name "BAT_GND") (class "Default")
      (node (ref "C10") (pin "1") (pinfunction "1_1") (pintype "passive"))
      (node (ref "C20") (pin "2") (pinfunction "2_2") (pintype "passive"))
      (node (ref "C25") (pin "2") (pinfunction "2_2") (pintype "passive"))
      (node (ref "C32") (pin "2") (pinfunction "2_2") (pintype "passive"))
      (node (ref "C33") (pin "2") (pinfunction "2_2") (pintype "passive"))
      (node (ref "C41") (pin "1") (pinfunction "1_1") (pintype "passive"))
      (node (ref "C49") (pin "1") (pinfunction "1_1") (pintype "passive"))
      (node (ref "C7") (pin "1") (pinfunction "1_1") (pintype "passive"))
      (node (ref "J15") (pin "3") (pinfunction "3_3") (pintype "power_in"))
      (node (ref "J16") (pin "2") (pinfunction "2_2") (pintype "passive"))
      (node (ref "J18") (pin "1") (pinfunction "1_1") (pintype "passive"))
      (node (ref "Q1") (pin "1") (pinfunction "1_1") (pintype "passive"))
      (node (ref "Q1") (pin "2") (pinfunction "2_2") (pintype "passive"))
      (node (ref "Q1") (pin "3") (pinfunction "3_3") (pintype "passive"))
      (node (ref "Q4") (pin "2") (pinfunction "S_2") (pintype "passive"))
      (node (ref "R29") (pin "2") (pinfunction "2_2") (pintype "passive"))
      (node (ref "R31") (pin "2") (pinfunction "2_2") (pintype "passive"))
      (node (ref "R33") (pin "2") (pinfunction "2_2") (pintype "passive"))
      (node (ref "R5") (pin "1") (pinfunction "1_1") (pintype "passive"))
      (node (ref "U10") (pin "3") (pinfunction "GND_3") (pintype "power_in"))
      (node (ref "U12") (pin "3") (pinfunction "GND_3") (pintype "power_in"))
      (node (ref "U3") (pin "4") (pinfunction "GND_4") (pintype "passive"))
      (node (ref "U4") (pin "4") (pinfunction "GND_4") (pintype "passive"))
      (node (ref "U7") (pin "8") (pinfunction "VSS_8") (pintype "passive"))
      (node (ref "U8") (pin "6") (pinfunction "VSS_6") (pintype "passive"))
      (node (ref "U9") (pin "3") (pinfunction "VSS_3") (pintype "passive"))
    )
    (net (code "13") (name "BM") (class "Default")
      (node (ref "C10") (pin "2") (pinfunction "2_2") (pintype "passive"))
      (node (ref "C3") (pin "2") (pinfunction "2_2") (pintype "passive"))
      (node (ref "C41") (pin "2") (pinfunction "2_2") (pintype "passive"))
      (node (ref "C49") (pin "2") (pinfunction "2_2") (pintype "passive"))
      (node (ref "C6") (pin "2") (pinfunction "2_2") (pintype "passive"))
      (node (ref "J15") (pin "2") (pinfunction "2_2") (pintype "power_in"))
      (node (ref "Q2") (pin "2") (pinfunction "S_2") (pintype "passive"))
      (node (ref "R10") (pin "1") (pinfunction "1_1") (pintype "passive"))
      (node (ref "R11") (pin "1") (pinfunction "1_1") (pintype "passive"))
      (node (ref "R21") (pin "1") (pinfunction "1_1") (pintype "passive"))
      (node (ref "R4") (pin "2") (pinfunction "2_2") (pintype "passive"))
      (node (ref "R7") (pin "2") (pinfunction "2_2") (pintype "passive"))
      (node (ref "R8") (pin "2") (pinfunction "2_2") (pintype "passive"))
      (node (ref "R9") (pin "1") (pinfunction "1_1") (pintype "passive"))
      (node (ref "SB1") (pin "1") (pinfunction "A_1") (pintype "passive"))
      (node (ref "SB2") (pin "1") (pinfunction "A_1") (pintype "passive"))
      (node (ref "U1") (pin "6") (pinfunction "VSS_6") (pintype "passive"))
      (node (ref "U10") (pin "5") (pinfunction "VCC_5") (pintype "power_in"))
      (node (ref "U12") (pin "5") (pinfunction "VCC_5") (pintype "power_in"))
      (node (ref "U2") (pin "3") (pinfunction "VSS_3") (pintype "passive"))
      (node (ref "U4") (pin "8") (pinfunction "VCC_8") (pintype "passive"))
    )
    (net (code "14") (name "GND") (class "Default")
      (node (ref "C1") (pin "2") (pinfunction "2_2") (pintype "passive"))
      (node (ref "C11") (pin "2") (pinfunction "2_2") (pintype "passive"))
      (node (ref "C12") (pin "2") (pinfunction "2_2") (pintype "passive"))
      (node (ref "C13") (pin "2") (pinfunction "2_2") (pintype "passive"))
      (node (ref "C14") (pin "2") (pinfunction "2_2") (pintype "passive"))
      (node (ref "C15") (pin "2") (pinfunction "2_2") (pintype "passive"))
      (node (ref "C16") (pin "2") (pinfunction "2_2") (pintype "passive"))
      (node (ref "C17") (pin "2") (pinfunction "2_2") (pintype "passive"))
      (node (ref "C18") (pin "2") (pinfunction "2_2") (pintype "passive"))
      (node (ref "C19") (pin "2") (pinfunction "2_2") (pintype "passive"))
      (node (ref "C2") (pin "2") (pinfunction "2_2") (pintype "passive"))
      (node (ref "C21") (pin "2") (pinfunction "2_2") (pintype "passive"))
      (node (ref "C22") (pin "2") (pinfunction "2_2") (pintype "passive"))
      (node (ref "C23") (pin "2") (pinfunction "2_2") (pintype "passive"))
      (node (ref "C24") (pin "2") (pinfunction "2_2") (pintype "passive"))
      (node (ref "C26") (pin "2") (pinfunction "2_2") (pintype "passive"))
      (node (ref "C27") (pin "2") (pinfunction "2_2") (pintype "passive"))
      (node (ref "C28") (pin "2") (pinfunction "2_2") (pintype "passive"))
      (node (ref "C29") (pin "2") (pinfunction "2_2") (pintype "passive"))
      (node (ref "C30") (pin "2") (pinfunction "2_2") (pintype "passive"))
      (node (ref "C34") (pin "2") (pinfunction "2_2") (pintype "passive"))
      (node (ref "C35") (pin "2") (pinfunction "2_2") (pintype "passive"))
      (node (ref "C36") (pin "2") (pinfunction "2_2") (pintype "passive"))
      (node (ref "C37") (pin "2") (pinfunction "2_2") (pintype "passive"))
      (node (ref "C38") (pin "2") (pinfunction "2_2") (pintype "passive"))
      (node (ref "C39") (pin "2") (pinfunction "2_2") (pintype "passive"))
      (node (ref "C4") (pin "2") (pinfunction "2_2") (pintype "passive"))
      (node (ref "C40") (pin "2") (pinfunction "2_2") (pintype "passive"))
      (node (ref "C42") (pin "2") (pinfunction "2_2") (pintype "passive"))
      (node (ref "C43") (pin "2") (pinfunction "2_2") (pintype "passive"))
      (node (ref "C44") (pin "2") (pinfunction "2_2") (pintype "passive"))
      (node (ref "C45") (pin "2") (pinfunction "2_2") (pintype "passive"))
      (node (ref "C46") (pin "2") (pinfunction "2_2") (pintype "passive"))
      (node (ref "C47") (pin "2") (pinfunction "2_2") (pintype "passive"))
      (node (ref "C5") (pin "2") (pinfunction "2_2") (pintype "passive"))
      (node (ref "C8") (pin "2") (pinfunction "2_2") (pintype "passive"))
      (node (ref "C9") (pin "2") (pinfunction "2_2") (pintype "passive"))
      (node (ref "J1") (pin "1") (pinfunction "1_1") (pintype "passive"))
      (node (ref "J10") (pin "1") (pinfunction "1_1") (pintype "passive"))
      (node (ref "J11") (pin "1") (pinfunction "1_1") (pintype "passive"))
      (node (ref "J12") (pin "1") (pinfunction "1_1") (pintype "passive"))
      (node (ref "J13") (pin "1") (pinfunction "1_1") (pintype "passive"))
      (node (ref "J14") (pin "1") (pinfunction "1_1") (pintype "passive"))
      (node (ref "J17") (pin "1") (pinfunction "1_1") (pintype "passive"))
      (node (ref "J20") (pin "1") (pinfunction "1_1") (pintype "passive"))
      (node (ref "J3") (pin "1") (pinfunction "1_1") (pintype "passive"))
      (node (ref "J4") (pin "1") (pinfunction "1_1") (pintype "passive"))
      (node (ref "J5") (pin "1") (pinfunction "1_1") (pintype "passive"))
      (node (ref "J6") (pin "1") (pinfunction "1_1") (pintype "passive"))
      (node (ref "J7") (pin "1") (pinfunction "1_1") (pintype "passive"))
      (node (ref "J8") (pin "1") (pinfunction "1_1") (pintype "passive"))
      (node (ref "J9") (pin "1") (pinfunction "1_1") (pintype "passive"))
      (node (ref "Q1") (pin "5") (pinfunction "5_5") (pintype "passive"))
      (node (ref "Q1") (pin "6") (pinfunction "6_6") (pintype "passive"))
      (node (ref "Q1") (pin "7") (pinfunction "7_7") (pintype "passive"))
      (node (ref "Q1") (pin "8") (pinfunction "8_8") (pintype "passive"))
      (node (ref "R14") (pin "2") (pinfunction "2_2") (pintype "passive"))
      (node (ref "R17") (pin "2") (pinfunction "2_2") (pintype "passive"))
      (node (ref "R18") (pin "2") (pinfunction "2_2") (pintype "passive"))
      (node (ref "R23") (pin "2") (pinfunction "2_2") (pintype "passive"))
      (node (ref "R26") (pin "2") (pinfunction "2_2") (pintype "passive"))
      (node (ref "R27") (pin "2") (pinfunction "2_2") (pintype "passive"))
      (node (ref "R28") (pin "1") (pinfunction "1_1") (pintype "passive"))
      (node (ref "U11") (pin "3") (pinfunction "GND_3") (pintype "power_in"))
      (node (ref "U5") (pin "2") (pinfunction "GND_2") (pintype "power_in"))
      (node (ref "U6") (pin "3") (pinfunction "GND_3") (pintype "power_in"))
      (node (ref "U6") (pin "4") (pinfunction "AGND_4") (pintype "power_in"))
    )
    (net (code "15") (name "Net-(C1-Pad1)") (class "Default")
      (node (ref "C1") (pin "1") (pinfunction "1_1") (pintype "passive"))
      (node (ref "C2") (pin "1") (pinfunction "1_1") (pintype "passive"))
      (node (ref "F1") (pin "2") (pinfunction "2_2") (pintype "passive"))
      (node (ref "J1") (pin "2") (pinfunction "2_2") (pintype "passive"))
    )
    (net (code "16") (name "Net-(C4-Pad1)") (class "Default")
      (node (ref "C4") (pin "1") (pinfunction "1_1") (pintype "passive"))
      (node (ref "C5") (pin "1") (pinfunction "1_1") (pintype "passive"))
      (node (ref "F2") (pin "2") (pinfunction "2_2") (pintype "passive"))
      (node (ref "J4") (pin "2") (pinfunction "2_2") (pintype "passive"))
    )
    (net (code "17") (name "Net-(C8-Pad1)") (class "Default")
      (node (ref "C8") (pin "1") (pinfunction "1_1") (pintype "passive"))
      (node (ref "C9") (pin "1") (pinfunction "1_1") (pintype "passive"))
      (node (ref "F3") (pin "2") (pinfunction "2_2") (pintype "passive"))
      (node (ref "J5") (pin "2") (pinfunction "2_2") (pintype "passive"))
    )
    (net (code "18") (name "Net-(C11-Pad1)") (class "Default")
      (node (ref "C11") (pin "1") (pinfunction "1_1") (pintype "passive"))
      (node (ref "C12") (pin "1") (pinfunction "1_1") (pintype "passive"))
      (node (ref "F4") (pin "2") (pinfunction "2_2") (pintype "passive"))
      (node (ref "J7") (pin "2") (pinfunction "2_2") (pintype "passive"))
    )
    (net (code "19") (name "Net-(C13-Pad1)") (class "Default")
      (node (ref "C13") (pin "1") (pinfunction "1_1") (pintype "passive"))
      (node (ref "C14") (pin "1") (pinfunction "1_1") (pintype "passive"))
      (node (ref "F5") (pin "2") (pinfunction "2_2") (pintype "passive"))
      (node (ref "J8") (pin "2") (pinfunction "2_2") (pintype "passive"))
    )
    (net (code "20") (name "Net-(C15-Pad1)") (class "Default")
      (node (ref "C15") (pin "1") (pinfunction "1_1") (pintype "passive"))
      (node (ref "C16") (pin "1") (pinfunction "1_1") (pintype "passive"))
      (node (ref "F6") (pin "2") (pinfunction "2_2") (pintype "passive"))
      (node (ref "J9") (pin "2") (pinfunction "2_2") (pintype "passive"))
    )
    (net (code "21") (name "Net-(C17-Pad1)") (class "Default")
      (node (ref "C17") (pin "1") (pinfunction "1_1") (pintype "passive"))
      (node (ref "C18") (pin "1") (pinfunction "1_1") (pintype "passive"))
      (node (ref "F7") (pin "2") (pinfunction "2_2") (pintype "passive"))
      (node (ref "J10") (pin "2") (pinfunction "2_2") (pintype "passive"))
    )
    (net (code "22") (name "Net-(C19-Pad1)") (class "Default")
      (node (ref "C19") (pin "1") (pinfunction "1_1") (pintype "passive"))
      (node (ref "C22") (pin "1") (pinfunction "1_1") (pintype "passive"))
      (node (ref "F8") (pin "2") (pinfunction "2_2") (pintype "passive"))
      (node (ref "J11") (pin "2") (pinfunction "2_2") (pintype "passive"))
    )
    (net (code "23") (name "Net-(C23-Pad1)") (class "Default")
      (node (ref "C23") (pin "1") (pinfunction "1_1") (pintype "passive"))
      (node (ref "C24") (pin "1") (pinfunction "1_1") (pintype "passive"))
      (node (ref "F9") (pin "2") (pinfunction "2_2") (pintype "passive"))
      (node (ref "J12") (pin "2") (pinfunction "2_2") (pintype "passive"))
    )
    (net (code "24") (name "Net-(C27-Pad1)") (class "Default")
      (node (ref "C27") (pin "1") (pinfunction "1_1") (pintype "passive"))
      (node (ref "J2") (pin "2") (pinfunction "2_2") (pintype "passive"))
      (node (ref "R20") (pin "2") (pinfunction "2_2") (pintype "passive"))
      (node (ref "R28") (pin "2") (pinfunction "2_2") (pintype "passive"))
    )
    (net (code "25") (name "Net-(C28-Pad1)") (class "Default")
      (node (ref "C28") (pin "1") (pinfunction "1_1") (pintype "passive"))
      (node (ref "J2") (pin "1") (pinfunction "1_1") (pintype "passive"))
      (node (ref "R21") (pin "2") (pinfunction "2_2") (pintype "passive"))
    )
    (net (code "26") (name "Net-(D1-A)") (class "Default")
      (node (ref "D1") (pin "2") (pinfunction "A_2") (pintype "passive"))
      (node (ref "L1") (pin "2") (pinfunction "2_2") (pintype "passive"))
      (node (ref "U5") (pin "1") (pinfunction "SW_1") (pintype "power_in"))
    )
    (net (code "27") (name "Net-(Q1-Pad4)") (class "Default")
      (node (ref "Q1") (pin "4") (pinfunction "4_4") (pintype "passive"))
      (node (ref "R32") (pin "1") (pinfunction "1_1") (pintype "passive"))
    )
    (net (code "28") (name "Net-(Q2-D)") (class "Default")
      (node (ref "Q2") (pin "3") (pinfunction "D_3") (pintype "passive"))
      (node (ref "R3") (pin "2") (pinfunction "2_2") (pintype "passive"))
    )
    (net (code "29") (name "Net-(Q3-GATE)") (class "Default")
      (node (ref "Q3") (pin "1") (pinfunction "GATE_1") (pintype "passive"))
      (node (ref "U7") (pin "10") (pinfunction "DRV_10") (pintype "passive"))
    )
    (net (code "30") (name "Net-(Q3-SOURCE)") (class "Default")
      (node (ref "Q3") (pin "3") (pinfunction "SOURCE_3") (pintype "passive"))
      (node (ref "R19") (pin "2") (pinfunction "2_2") (pintype "passive"))
      (node (ref "U7") (pin "1") (pinfunction "SENSE_1") (pintype "passive"))
    )
    (net (code "31") (name "Net-(Q4-D)") (class "Default")
      (node (ref "Q4") (pin "3") (pinfunction "D_3") (pintype "passive"))
      (node (ref "R9") (pin "2") (pinfunction "2_2") (pintype "passive"))
    )
    (net (code "32") (name "Net-(R5-Pad2)") (class "Default")
      (node (ref "R5") (pin "2") (pinfunction "2_2") (pintype "passive"))
      (node (ref "R6") (pin "1") (pinfunction "1_1") (pintype "passive"))
      (node (ref "U3") (pin "2") (pinfunction "2_2") (pintype "passive"))
      (node (ref "U3") (pin "6") (pinfunction "6_6") (pintype "passive"))
    )
    (net (code "33") (name "Net-(SB1-B)") (class "Default")
      (node (ref "R32") (pin "2") (pinfunction "2_2") (pintype "passive"))
      (node (ref "R33") (pin "1") (pinfunction "1_1") (pintype "passive"))
      (node (ref "SB1") (pin "2") (pinfunction "B_2") (pintype "passive"))
      (node (ref "TP8") (pin "1") (pinfunction "1_1") (pintype "passive"))
      (node (ref "U12") (pin "4") (pinfunction "Y_4") (pintype "output"))
    )
    (net (code "34") (name "Net-(SB2-B)") (class "Default")
      (node (ref "R30") (pin "1") (pinfunction "1_1") (pintype "passive"))
      (node (ref "SB2") (pin "2") (pinfunction "B_2") (pintype "passive"))
      (node (ref "U7") (pin "5") (pinfunction "THREF_5") (pintype "passive"))
    )
    (net (code "35") (name "Net-(U1-CSI)") (class "Default")
      (node (ref "R4") (pin "1") (pinfunction "1_1") (pintype "passive"))
      (node (ref "U1") (pin "2") (pinfunction "CSI_2") (pintype "passive"))
    )
    (net (code "36") (name "Net-(U1-VDD)") (class "Default")
      (node (ref "C3") (pin "1") (pinfunction "1_1") (pintype "passive"))
      (node (ref "R1") (pin "1") (pinfunction "1_1") (pintype "passive"))
      (node (ref "U1") (pin "5") (pinfunction "VDD_5") (pintype "passive"))
    )
    (net (code "37") (name "Net-(U2-VDD)") (class "Default")
      (node (ref "C6") (pin "1") (pinfunction "1_1") (pintype "passive"))
      (node (ref "R2") (pin "1") (pinfunction "1_1") (pintype "passive"))
      (node (ref "U2") (pin "2") (pinfunction "VDD_2") (pintype "passive"))
    )
    (net (code "38") (name "Net-(U4-1B)") (class "Default")
      (node (ref "R10") (pin "2") (pinfunction "2_2") (pintype "passive"))
      (node (ref "TP6") (pin "1") (pinfunction "1_1") (pintype "passive"))
      (node (ref "U3") (pin "7") (pinfunction "7_7") (pintype "passive"))
      (node (ref "U4") (pin "2") (pinfunction "1B_2") (pintype "passive"))
    )
    (net (code "39") (name "Net-(U5-FB)") (class "Default")
      (node (ref "R13") (pin "2") (pinfunction "2_2") (pintype "passive"))
      (node (ref "R14") (pin "1") (pinfunction "1_1") (pintype "passive"))
      (node (ref "U5") (pin "3") (pinfunction "FB_3") (pintype "passive"))
    )
    (net (code "40") (name "Net-(U6-EN)") (class "Default")
      (node (ref "R22") (pin "2") (pinfunction "2_2") (pintype "passive"))
      (node (ref "R23") (pin "1") (pinfunction "1_1") (pintype "passive"))
      (node (ref "U6") (pin "5") (pinfunction "EN_5") (pintype "input"))
    )
    (net (code "41") (name "Net-(U6-FB)") (class "Default")
      (node (ref "C31") (pin "2") (pinfunction "2_2") (pintype "passive"))
      (node (ref "R16") (pin "2") (pinfunction "2_2") (pintype "passive"))
      (node (ref "R18") (pin "1") (pinfunction "1_1") (pintype "passive"))
      (node (ref "U6") (pin "6") (pinfunction "FB_6") (pintype "input"))
    )
    (net (code "42") (name "Net-(U6-SW)") (class "Default")
      (node (ref "L2") (pin "1") (pinfunction "1_1") (pintype "passive"))
      (node (ref "U6") (pin "2") (pinfunction "SW_2") (pintype "output"))
    )
    (net (code "43") (name "Net-(U7-TIMER)") (class "Default")
      (node (ref "C33") (pin "1") (pinfunction "1_1") (pintype "passive"))
      (node (ref "U7") (pin "7") (pinfunction "TIMER_7") (pintype "passive"))
    )
    (net (code "44") (name "Net-(U8-CSI)") (class "Default")
      (node (ref "R17") (pin "1") (pinfunction "1_1") (pintype "passive"))
      (node (ref "U8") (pin "2") (pinfunction "CSI_2") (pintype "passive"))
    )
    (net (code "45") (name "Net-(U8-VDD)") (class "Default")
      (node (ref "C20") (pin "1") (pinfunction "1_1") (pintype "passive"))
      (node (ref "R7") (pin "1") (pinfunction "1_1") (pintype "passive"))
      (node (ref "U8") (pin "5") (pinfunction "VDD_5") (pintype "passive"))
    )
    (net (code "46") (name "Net-(U9-VDD)") (class "Default")
      (node (ref "C25") (pin "1") (pinfunction "1_1") (pintype "passive"))
      (node (ref "R8") (pin "1") (pinfunction "1_1") (pintype "passive"))
      (node (ref "U9") (pin "2") (pinfunction "VDD_2") (pintype "passive"))
    )
    (net (code "47") (name "Net-(U10-Y)") (class "Default")
      (node (ref "U10") (pin "4") (pinfunction "Y_4") (pintype "output"))
      (node (ref "U7") (pin "4") (pinfunction "EN_4") (pintype "passive"))
    )
    (net (code "48") (name "Net-(U11-EN)") (class "Default")
      (node (ref "R24") (pin "2") (pinfunction "2_2") (pintype "passive"))
      (node (ref "R26") (pin "1") (pinfunction "1_1") (pintype "passive"))
      (node (ref "U11") (pin "5") (pinfunction "EN_5") (pintype "input"))
    )
    (net (code "49") (name "Net-(U11-FB)") (class "Default")
      (node (ref "C48") (pin "2") (pinfunction "2_2") (pintype "passive"))
      (node (ref "R25") (pin "2") (pinfunction "2_2") (pintype "passive"))
      (node (ref "R27") (pin "1") (pinfunction "1_1") (pintype "passive"))
      (node (ref "U11") (pin "6") (pinfunction "FB_6") (pintype "input"))
    )
    (net (code "50") (name "Net-(U11-SW)") (class "Default")
      (node (ref "L3") (pin "2") (pinfunction "2_2") (pintype "passive"))
      (node (ref "U11") (pin "2") (pinfunction "SW_2") (pintype "output"))
    )
    (net (code "51") (name "VBAT") (class "Default")
      (node (ref "C26") (pin "1") (pinfunction "1_1") (pintype "passive"))
      (node (ref "C29") (pin "1") (pinfunction "1_1") (pintype "passive"))
      (node (ref "C32") (pin "1") (pinfunction "1_1") (pintype "passive"))
      (node (ref "C34") (pin "1") (pinfunction "1_1") (pintype "passive"))
      (node (ref "C35") (pin "1") (pinfunction "1_1") (pintype "passive"))
      (node (ref "C36") (pin "1") (pinfunction "1_1") (pintype "passive"))
      (node (ref "C7") (pin "2") (pinfunction "2_2") (pintype "passive"))
      (node (ref "F1") (pin "1") (pinfunction "1_1") (pintype "passive"))
      (node (ref "F2") (pin "1") (pinfunction "1_1") (pintype "passive"))
      (node (ref "F3") (pin "1") (pinfunction "1_1") (pintype "passive"))
      (node (ref "F4") (pin "1") (pinfunction "1_1") (pintype "passive"))
      (node (ref "F5") (pin "1") (pinfunction "1_1") (pintype "passive"))
      (node (ref "F6") (pin "1") (pinfunction "1_1") (pintype "passive"))
      (node (ref "F7") (pin "1") (pinfunction "1_1") (pintype "passive"))
      (node (ref "F8") (pin "1") (pinfunction "1_1") (pintype "passive"))
      (node (ref "F9") (pin "1") (pinfunction "1_1") (pintype "passive"))
      (node (ref "J15") (pin "1") (pinfunction "1_1") (pintype "power_in"))
      (node (ref "J16") (pin "1") (pinfunction "1_1") (pintype "passive"))
      (node (ref "L1") (pin "1") (pinfunction "1_1") (pintype "passive"))
      (node (ref "Q3") (pin "2") (pinfunction "DRAIN_2") (pintype "passive"))
      (node (ref "R1") (pin "2") (pinfunction "2_2") (pintype "passive"))
      (node (ref "R2") (pin "2") (pinfunction "2_2") (pintype "passive"))
      (node (ref "R20") (pin "1") (pinfunction "1_1") (pintype "passive"))
      (node (ref "R22") (pin "1") (pinfunction "1_1") (pintype "passive"))
      (node (ref "R3") (pin "1") (pinfunction "1_1") (pintype "passive"))
      (node (ref "R6") (pin "2") (pinfunction "2_2") (pintype "passive"))
      (node (ref "U3") (pin "8") (pinfunction "VCC_8") (pintype "passive"))
      (node (ref "U5") (pin "4") (pinfunction "EN_4") (pintype "input"))
      (node (ref "U5") (pin "5") (pinfunction "VIN_5") (pintype "power_in"))
      (node (ref "U6") (pin "1") (pinfunction "VIN_1") (pintype "input"))
      (node (ref "U7") (pin "9") (pinfunction "VBAT_9") (pintype "passive"))
    )
    (net (code "52") (name "VCHG") (class "Default")
      (node (ref "C42") (pin "1") (pinfunction "1_1") (pintype "passive"))
      (node (ref "C43") (pin "1") (pinfunction "1_1") (pintype "passive"))
      (node (ref "J20") (pin "2") (pinfunction "2_2") (pintype "passive"))
      (node (ref "R24") (pin "1") (pinfunction "1_1") (pintype "passive"))
      (node (ref "U11") (pin "1") (pinfunction "VIN_1") (pintype "input"))
    )
    (net (code "53") (name "unconnected-(U1-OC-Pad3)") (class "Default")
      (node (ref "U1") (pin "3") (pinfunction "OC_3") (pintype "passive+no_connect"))
    )
    (net (code "54") (name "unconnected-(U1-TD-Pad4)") (class "Default")
      (node (ref "U1") (pin "4") (pinfunction "TD_4") (pintype "passive+no_connect"))
    )
    (net (code "55") (name "unconnected-(U2-DS-Pad4)") (class "Default")
      (node (ref "U2") (pin "4") (pinfunction "DS_4") (pintype "passive+no_connect"))
    )
    (net (code "56") (name "unconnected-(U2-NC-Pad1)") (class "Default")
      (node (ref "U2") (pin "1") (pinfunction "NC_1") (pintype "passive+no_connect"))
    )
    (net (code "57") (name "unconnected-(U4-2A-Pad5)") (class "Default")
      (node (ref "U4") (pin "5") (pinfunction "2A_5") (pintype "passive+no_connect"))
    )
    (net (code "58") (name "unconnected-(U4-2B-Pad6)") (class "Default")
      (node (ref "U4") (pin "6") (pinfunction "2B_6") (pintype "passive+no_connect"))
    )
    (net (code "59") (name "unconnected-(U4-2Y-Pad3)") (class "Default")
      (node (ref "U4") (pin "3") (pinfunction "2Y_3") (pintype "passive+no_connect"))
    )
    (net (code "60") (name "unconnected-(U8-OC-Pad3)") (class "Default")
      (node (ref "U8") (pin "3") (pinfunction "OC_3") (pintype "passive+no_connect"))
    )
    (net (code "61") (name "unconnected-(U8-TD-Pad4)") (class "Default")
      (node (ref "U8") (pin "4") (pinfunction "TD_4") (pintype "passive+no_connect"))
    )
    (net (code "62") (name "unconnected-(U9-DS-Pad4)") (class "Default")
      (node (ref "U9") (pin "4") (pinfunction "DS_4") (pintype "passive+no_connect"))
    )
    (net (code "63") (name "unconnected-(U9-NC-Pad1)") (class "Default")
      (node (ref "U9") (pin "1") (pinfunction "NC_1") (pintype "passive+no_connect"))
    )
    (net (code "64") (name "unconnected-(U10-NC-Pad1)") (class "Default")
      (node (ref "U10") (pin "1") (pinfunction "NC_1") (pintype "passive+no_connect"))
    )
    (net (code "65") (name "unconnected-(U11-PG-Pad4)") (class "Default")
      (node (ref "U11") (pin "4") (pinfunction "PG_4") (pintype "power_in+no_connect"))
    )
  )
)
